# Artemis_Corner_Board_V2_FR.net
KiCad netlist of a schematic drawn in EAGLE
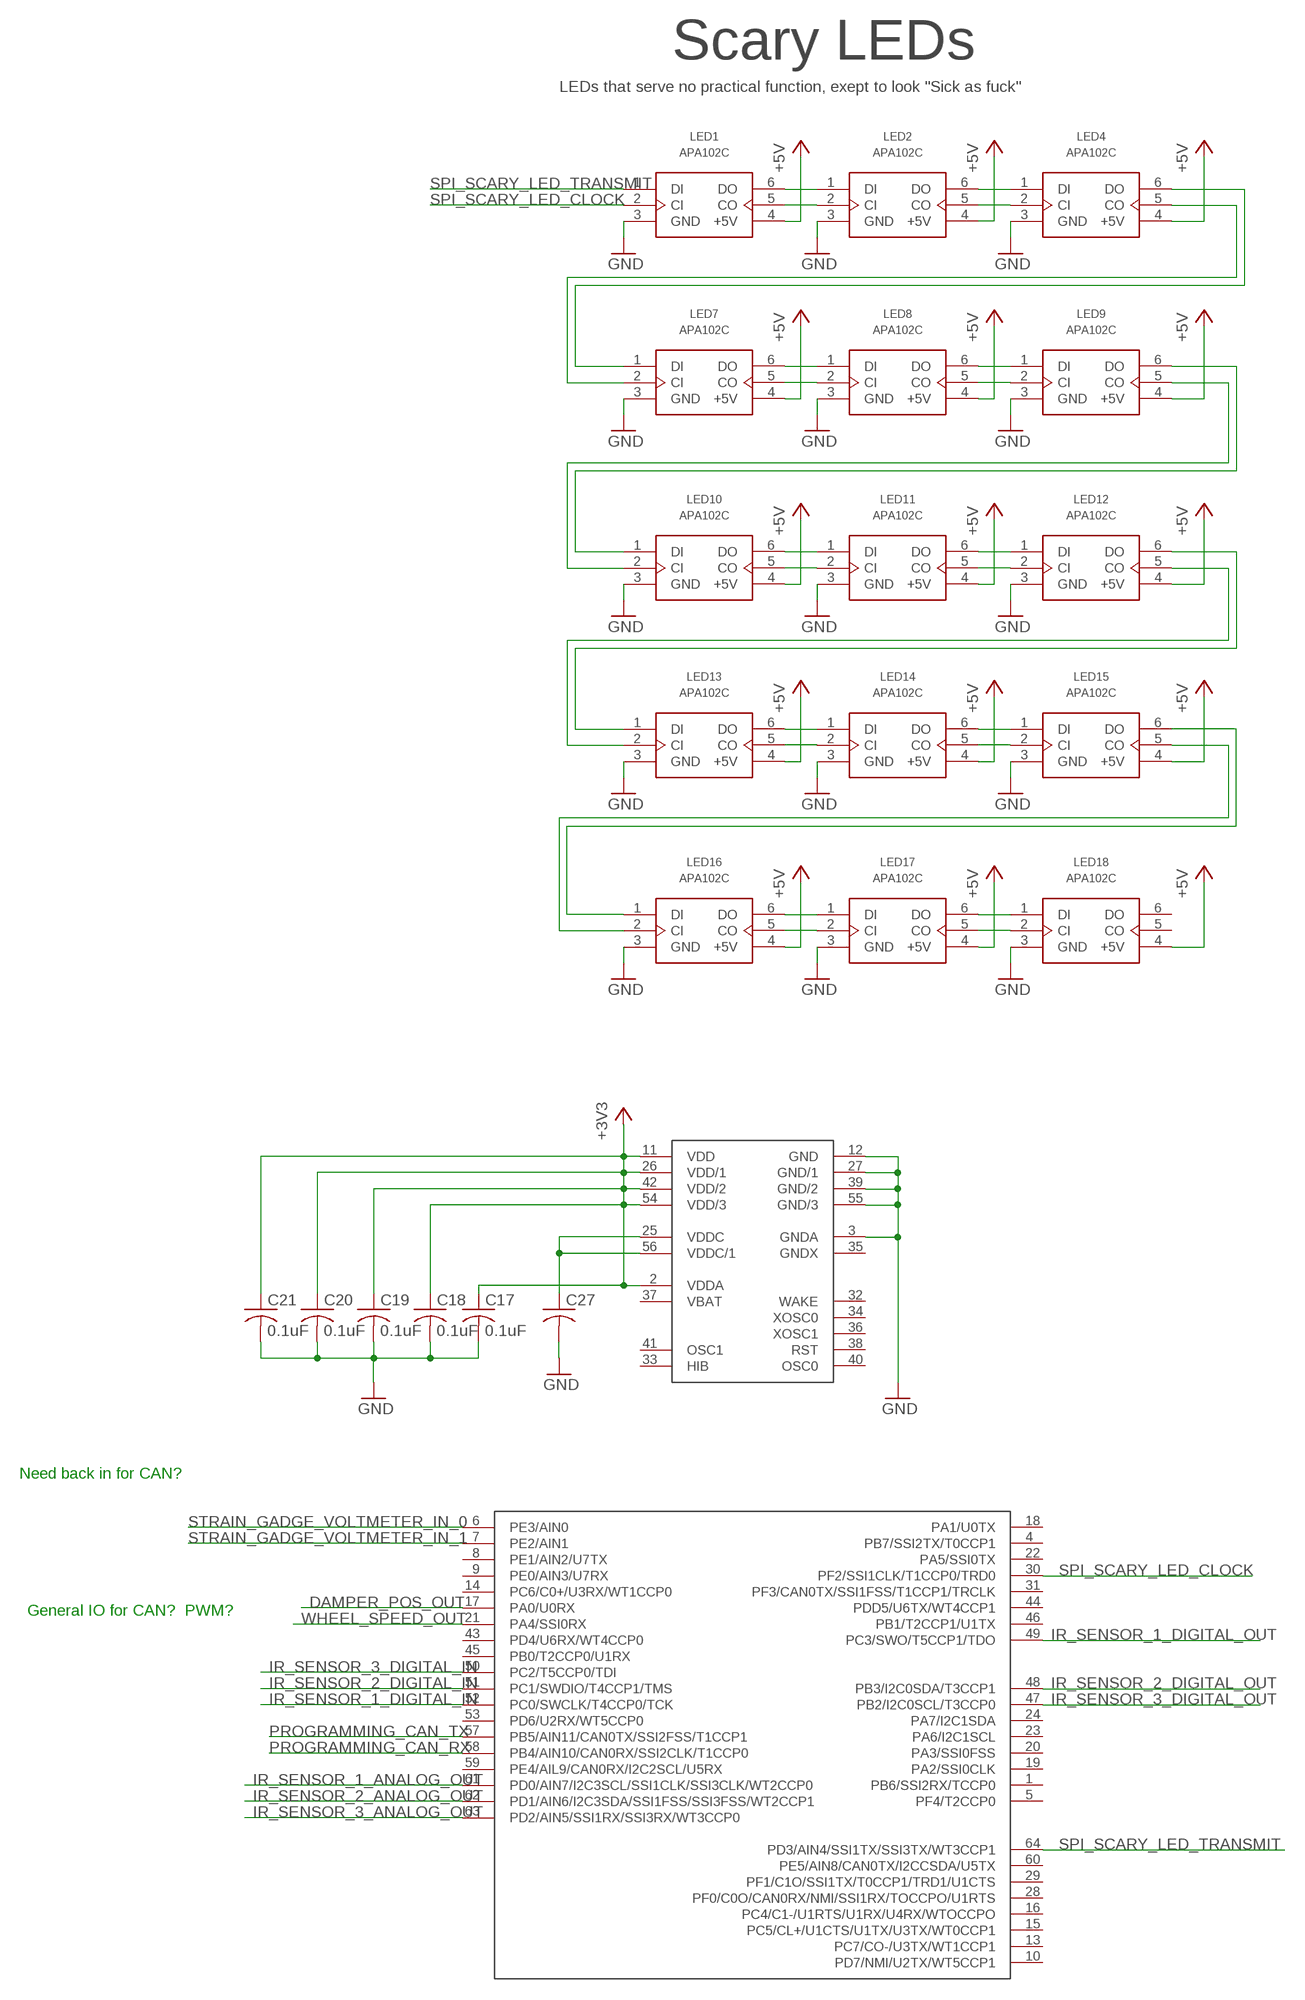
[diagram p0: schematic, sheet 1, part 1 of 2]
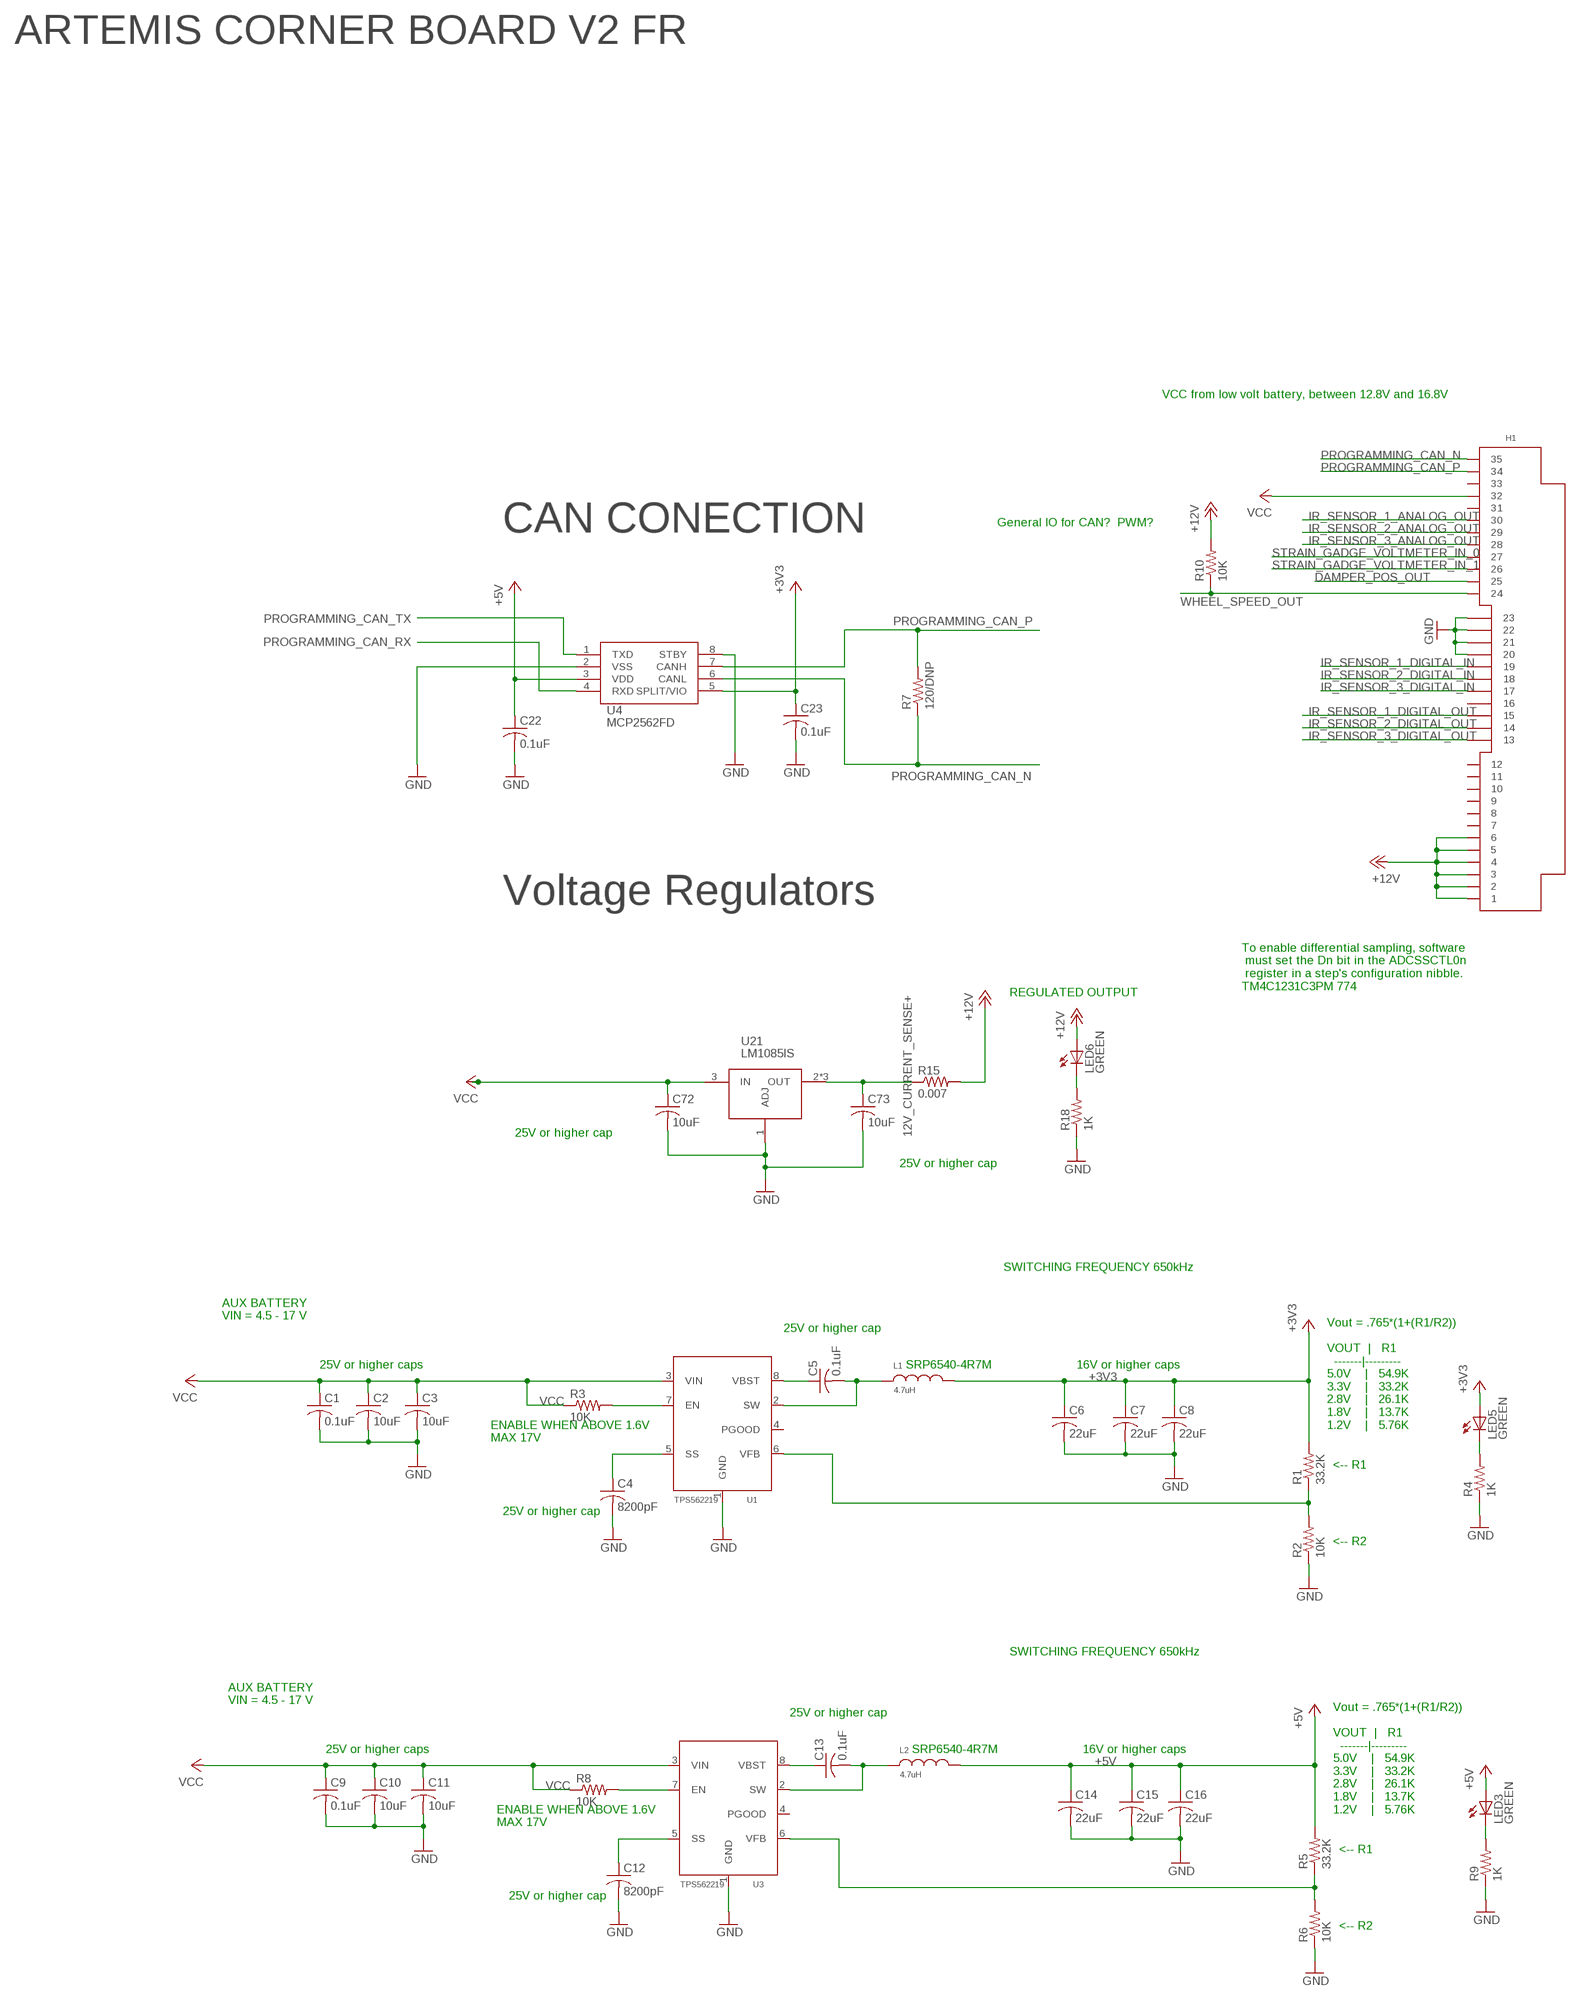
[diagram p1: schematic, sheet 1, part 2 of 2]

(export (version "E")
  (design (tool "Eeschema 10.0.6"))
  (components
    (comp (ref "C1")
      (value "0.1uF")
      (footprint "eagle-import:C0805")
      (fields (field (name "PARTNO") "GRM21BR71E104KA01L"))
      (libsource (lib "eagle-import") (part "C-USC0805"))
    )
    (comp (ref "C2")
      (value "10uF")
      (footprint "eagle-import:C0805")
      (fields (field (name "PARTNO") "GRM21BR61E106KA73L"))
      (libsource (lib "eagle-import") (part "C-USC0805"))
    )
    (comp (ref "C3")
      (value "10uF")
      (footprint "eagle-import:C0805")
      (fields (field (name "PARTNO") "GRM21BR61E106KA73L"))
      (libsource (lib "eagle-import") (part "C-USC0805"))
    )
    (comp (ref "C4")
      (value "8200pF")
      (footprint "eagle-import:C0805")
      (fields (field (name "PARTNO") "C0805C822K5RACTU"))
      (libsource (lib "eagle-import") (part "C-USC0805"))
    )
    (comp (ref "C5")
      (value "0.1uF")
      (footprint "eagle-import:C0805")
      (fields (field (name "PARTNO") "GRM21BR71E104KA01L"))
      (libsource (lib "eagle-import") (part "C-USC0805"))
    )
    (comp (ref "C6")
      (value "22uF")
      (footprint "eagle-import:C0805")
      (fields (field (name "PARTNO") "C2012JB1E226M125AC"))
      (libsource (lib "eagle-import") (part "C-USC0805"))
    )
    (comp (ref "C7")
      (value "22uF")
      (footprint "eagle-import:C0805")
      (fields (field (name "PARTNO") "C2012JB1E226M125AC"))
      (libsource (lib "eagle-import") (part "C-USC0805"))
    )
    (comp (ref "C8")
      (value "22uF")
      (footprint "eagle-import:C0805")
      (fields (field (name "PARTNO") "C2012JB1E226M125AC"))
      (libsource (lib "eagle-import") (part "C-USC0805"))
    )
    (comp (ref "C9")
      (value "0.1uF")
      (footprint "eagle-import:C0805")
      (fields (field (name "PARTNO") "GRM21BR71E104KA01L"))
      (libsource (lib "eagle-import") (part "C-USC0805"))
    )
    (comp (ref "C10")
      (value "10uF")
      (footprint "eagle-import:C0805")
      (fields (field (name "PARTNO") "GRM21BR61E106KA73L"))
      (libsource (lib "eagle-import") (part "C-USC0805"))
    )
    (comp (ref "C11")
      (value "10uF")
      (footprint "eagle-import:C0805")
      (fields (field (name "PARTNO") "GRM21BR61E106KA73L"))
      (libsource (lib "eagle-import") (part "C-USC0805"))
    )
    (comp (ref "C12")
      (value "8200pF")
      (footprint "eagle-import:C0805")
      (fields (field (name "PARTNO") "C0805C822K5RACTU"))
      (libsource (lib "eagle-import") (part "C-USC0805"))
    )
    (comp (ref "C13")
      (value "0.1uF")
      (footprint "eagle-import:C0805")
      (fields (field (name "PARTNO") "GRM21BR71E104KA01L"))
      (libsource (lib "eagle-import") (part "C-USC0805"))
    )
    (comp (ref "C14")
      (value "22uF")
      (footprint "eagle-import:C0805")
      (fields (field (name "PARTNO") "C2012JB1E226M125AC"))
      (libsource (lib "eagle-import") (part "C-USC0805"))
    )
    (comp (ref "C15")
      (value "22uF")
      (footprint "eagle-import:C0805")
      (fields (field (name "PARTNO") "C2012JB1E226M125AC"))
      (libsource (lib "eagle-import") (part "C-USC0805"))
    )
    (comp (ref "C16")
      (value "22uF")
      (footprint "eagle-import:C0805")
      (fields (field (name "PARTNO") "C2012JB1E226M125AC"))
      (libsource (lib "eagle-import") (part "C-USC0805"))
    )
    (comp (ref "C17")
      (value "0.1uF")
      (footprint "eagle-import:C0805")
      (fields (field (name "PARTNO") "GRM21BR71H104KA01L"))
      (libsource (lib "eagle-import") (part "rcl_C-USC0805"))
    )
    (comp (ref "C18")
      (value "0.1uF")
      (footprint "eagle-import:C0805")
      (fields (field (name "PARTNO") "GRM21BR71H104KA01L"))
      (libsource (lib "eagle-import") (part "rcl_C-USC0805"))
    )
    (comp (ref "C19")
      (value "0.1uF")
      (footprint "eagle-import:C0805")
      (fields (field (name "PARTNO") "GRM21BR71H104KA01L"))
      (libsource (lib "eagle-import") (part "rcl_C-USC0805"))
    )
    (comp (ref "C20")
      (value "0.1uF")
      (footprint "eagle-import:C0805")
      (fields (field (name "PARTNO") "GRM21BR71H104KA01L"))
      (libsource (lib "eagle-import") (part "rcl_C-USC0805"))
    )
    (comp (ref "C21")
      (value "0.1uF")
      (footprint "eagle-import:C0805")
      (fields (field (name "PARTNO") "GRM21BR71H104KA01L"))
      (libsource (lib "eagle-import") (part "rcl_C-USC0805"))
    )
    (comp (ref "C22")
      (value "0.1uF")
      (footprint "eagle-import:C0805")
      (fields (field (name "PARTNO") "GRM21BR71H104KA01L"))
      (libsource (lib "eagle-import") (part "rcl_C-USC0805"))
    )
    (comp (ref "C23")
      (value "0.1uF")
      (footprint "eagle-import:C0805")
      (fields (field (name "PARTNO") "GRM21BR71H104KA01L"))
      (libsource (lib "eagle-import") (part "rcl_C-USC0805"))
    )
    (comp (ref "C27")
      (value "3.3uF")
      (footprint "eagle-import:C0805")
      (fields (field (name "MPN") "C1005X7R1E104K050BB") (field (name "PARTNO") "GRM21BR71E104KA01L"))
      (libsource (lib "eagle-import") (part "rcl_C-USC0805"))
    )
    (comp (ref "C72")
      (value "10uF")
      (footprint "eagle-import:C0805")
      (fields (field (name "PARTNO") "GRM21BR61E106KA73L"))
      (libsource (lib "eagle-import") (part "C-USC0805"))
    )
    (comp (ref "C73")
      (value "10uF")
      (footprint "eagle-import:C0805")
      (fields (field (name "PARTNO") "GRM21BR61E106KA73L"))
      (libsource (lib "eagle-import") (part "C-USC0805"))
    )
    (comp (ref "H1")
      (value "1-776231-1")
      (footprint "eagle-import:1-776231-1")
      (libsource (lib "eagle-import") (part "1-776231-1"))
    )
    (comp (ref "L1")
      (value "4.7uH")
      (footprint "eagle-import:SRP6540")
      (fields (field (name "PARTNO") "SRP6540-4R7M"))
      (libsource (lib "eagle-import") (part "SRP6540"))
    )
    (comp (ref "L2")
      (value "4.7uH")
      (footprint "eagle-import:SRP6540")
      (fields (field (name "PARTNO") "SRP6540-4R7M"))
      (libsource (lib "eagle-import") (part "SRP6540"))
    )
    (comp (ref "LED1")
      (value "APA102C")
      (footprint "eagle-import:5050_LED")
      (libsource (lib "eagle-import") (part "APA102C"))
    )
    (comp (ref "LED2")
      (value "APA102C")
      (footprint "eagle-import:5050_LED")
      (libsource (lib "eagle-import") (part "APA102C"))
    )
    (comp (ref "LED3")
      (value "GREEN")
      (footprint "eagle-import:CHIPLED_0805")
      (fields (field (name "PARTNO") "598-8170-107F"))
      (libsource (lib "eagle-import") (part "LEDCHIPLED_0805"))
    )
    (comp (ref "LED4")
      (value "APA102C")
      (footprint "eagle-import:5050_LED")
      (libsource (lib "eagle-import") (part "APA102C"))
    )
    (comp (ref "LED5")
      (value "GREEN")
      (footprint "eagle-import:CHIPLED_0805")
      (fields (field (name "PARTNO") "598-8170-107F"))
      (libsource (lib "eagle-import") (part "LEDCHIPLED_0805"))
    )
    (comp (ref "LED6")
      (value "GREEN")
      (footprint "eagle-import:CHIPLED_0805")
      (fields (field (name "PARTNO") "598-8170-107F"))
      (libsource (lib "eagle-import") (part "LEDCHIPLED_0805"))
    )
    (comp (ref "LED7")
      (value "APA102C")
      (footprint "eagle-import:5050_LED")
      (libsource (lib "eagle-import") (part "APA102C"))
    )
    (comp (ref "LED8")
      (value "APA102C")
      (footprint "eagle-import:5050_LED")
      (libsource (lib "eagle-import") (part "APA102C"))
    )
    (comp (ref "LED9")
      (value "APA102C")
      (footprint "eagle-import:5050_LED")
      (libsource (lib "eagle-import") (part "APA102C"))
    )
    (comp (ref "LED10")
      (value "APA102C")
      (footprint "eagle-import:5050_LED")
      (libsource (lib "eagle-import") (part "APA102C"))
    )
    (comp (ref "LED11")
      (value "APA102C")
      (footprint "eagle-import:5050_LED")
      (libsource (lib "eagle-import") (part "APA102C"))
    )
    (comp (ref "LED12")
      (value "APA102C")
      (footprint "eagle-import:5050_LED")
      (libsource (lib "eagle-import") (part "APA102C"))
    )
    (comp (ref "LED13")
      (value "APA102C")
      (footprint "eagle-import:5050_LED")
      (libsource (lib "eagle-import") (part "APA102C"))
    )
    (comp (ref "LED14")
      (value "APA102C")
      (footprint "eagle-import:5050_LED")
      (libsource (lib "eagle-import") (part "APA102C"))
    )
    (comp (ref "LED15")
      (value "APA102C")
      (footprint "eagle-import:5050_LED")
      (libsource (lib "eagle-import") (part "APA102C"))
    )
    (comp (ref "LED16")
      (value "APA102C")
      (footprint "eagle-import:5050_LED")
      (libsource (lib "eagle-import") (part "APA102C"))
    )
    (comp (ref "LED17")
      (value "APA102C")
      (footprint "eagle-import:5050_LED")
      (libsource (lib "eagle-import") (part "APA102C"))
    )
    (comp (ref "LED18")
      (value "APA102C")
      (footprint "eagle-import:5050_LED")
      (libsource (lib "eagle-import") (part "APA102C"))
    )
    (comp (ref "R1")
      (value "33.2K")
      (footprint "eagle-import:R0805")
      (fields (field (name "PARTNO") "ERA-6AEB5492V"))
      (libsource (lib "eagle-import") (part "R-US_R0805"))
    )
    (comp (ref "R2")
      (value "10K")
      (footprint "eagle-import:R0805")
      (fields (field (name "PARTNO") "ERJ-6ENF1002V"))
      (libsource (lib "eagle-import") (part "R-US_R0805"))
    )
    (comp (ref "R3")
      (value "10K")
      (footprint "eagle-import:R0805")
      (fields (field (name "PARTNO") "ERJ-6ENF1002V"))
      (libsource (lib "eagle-import") (part "R-US_R0805"))
    )
    (comp (ref "R4")
      (value "1K")
      (footprint "eagle-import:R0805")
      (fields (field (name "PARTNO") "ERJ-6ENF1001V"))
      (libsource (lib "eagle-import") (part "R-US_R0805"))
    )
    (comp (ref "R5")
      (value "33.2K")
      (footprint "eagle-import:R0805")
      (fields (field (name "PARTNO") "ERA-6AEB5492V"))
      (libsource (lib "eagle-import") (part "R-US_R0805"))
    )
    (comp (ref "R6")
      (value "10K")
      (footprint "eagle-import:R0805")
      (fields (field (name "PARTNO") "ERJ-6ENF1002V"))
      (libsource (lib "eagle-import") (part "R-US_R0805"))
    )
    (comp (ref "R7")
      (value "120/DNP")
      (footprint "eagle-import:R0805")
      (libsource (lib "eagle-import") (part "rcl_R-US_R0805"))
    )
    (comp (ref "R8")
      (value "10K")
      (footprint "eagle-import:R0805")
      (fields (field (name "PARTNO") "ERJ-6ENF1002V"))
      (libsource (lib "eagle-import") (part "R-US_R0805"))
    )
    (comp (ref "R9")
      (value "1K")
      (footprint "eagle-import:R0805")
      (fields (field (name "PARTNO") "ERJ-6ENF1001V"))
      (libsource (lib "eagle-import") (part "R-US_R0805"))
    )
    (comp (ref "R10")
      (value "10K")
      (footprint "eagle-import:R0805")
      (fields (field (name "PARTNO") "ERJ-6ENF1002V"))
      (libsource (lib "eagle-import") (part "R-US_R0805"))
    )
    (comp (ref "R15")
      (value "0.007")
      (footprint "eagle-import:R0805")
      (fields (field (name "PARTNO") "PMR10EZPFU7L00"))
      (libsource (lib "eagle-import") (part "R-US_R0805"))
    )
    (comp (ref "R18")
      (value "1K")
      (footprint "eagle-import:R0805")
      (fields (field (name "PARTNO") "ERJ-6ENF1001V"))
      (libsource (lib "eagle-import") (part "R-US_R0805"))
    )
    (comp (ref "U1")
      (value "TPS562219")
      (footprint "eagle-import:TPS562219")
      (fields (field (name "PARTNO") "TPS562219DDFT"))
      (libsource (lib "eagle-import") (part "TPS562219"))
    )
    (comp (ref "U2")
      (value "TM4C1231C3PM")
      (footprint "eagle-import:TM4C1231C3PM")
      (libsource (lib "eagle-import") (part "TM4C1231C3PM"))
    )
    (comp (ref "U3")
      (value "TPS562219")
      (footprint "eagle-import:TPS562219")
      (fields (field (name "PARTNO") "TPS562219DDFT"))
      (libsource (lib "eagle-import") (part "TPS562219"))
    )
    (comp (ref "U4")
      (value "MCP2562FD")
      (footprint "eagle-import:SOIC8-N_MC")
      (fields (field (name "PARTNO") "MCP2562FD-E/SN"))
      (libsource (lib "eagle-import") (part "MCP256X-SOIC"))
    )
    (comp (ref "U21")
      (value "LM1085IS")
      (footprint "eagle-import:TO-263")
      (fields (field (name "PARTNO") "LM1085IS-12/NOPB"))
      (libsource (lib "eagle-import") (part "LM1085"))
    )
  )
  (nets
    (net (code "1") (name "+3V3") (class "Default")
      (node (ref "C17") (pin "1") (pinfunction "1_1") (pintype "passive"))
      (node (ref "C18") (pin "1") (pinfunction "1_1") (pintype "passive"))
      (node (ref "C19") (pin "1") (pinfunction "1_1") (pintype "passive"))
      (node (ref "C20") (pin "1") (pinfunction "1_1") (pintype "passive"))
      (node (ref "C21") (pin "1") (pinfunction "1_1") (pintype "passive"))
      (node (ref "C23") (pin "1") (pinfunction "1_1") (pintype "passive"))
      (node (ref "C6") (pin "1") (pinfunction "1_1") (pintype "passive"))
      (node (ref "C7") (pin "1") (pinfunction "1_1") (pintype "passive"))
      (node (ref "C8") (pin "1") (pinfunction "1_1") (pintype "passive"))
      (node (ref "L1") (pin "P$2") (pinfunction "P$2_P$2") (pintype "bidirectional"))
      (node (ref "LED5") (pin "A") (pinfunction "A_A") (pintype "passive"))
      (node (ref "R1") (pin "2") (pinfunction "2_2") (pintype "passive"))
      (node (ref "U2") (pin "11") (pinfunction "VDD_11") (pintype "bidirectional"))
      (node (ref "U2") (pin "2") (pinfunction "VDDA_2") (pintype "bidirectional"))
      (node (ref "U2") (pin "26") (pinfunction "VDD/1_26") (pintype "bidirectional"))
      (node (ref "U2") (pin "42") (pinfunction "VDD/2_42") (pintype "bidirectional"))
      (node (ref "U2") (pin "54") (pinfunction "VDD/3_54") (pintype "bidirectional"))
      (node (ref "U4") (pin "5") (pinfunction "SPLIT/VIO_5") (pintype "bidirectional"))
    )
    (net (code "2") (name "+5V") (class "Default")
      (node (ref "C14") (pin "1") (pinfunction "1_1") (pintype "passive"))
      (node (ref "C15") (pin "1") (pinfunction "1_1") (pintype "passive"))
      (node (ref "C16") (pin "1") (pinfunction "1_1") (pintype "passive"))
      (node (ref "C22") (pin "1") (pinfunction "1_1") (pintype "passive"))
      (node (ref "L2") (pin "P$2") (pinfunction "P$2_P$2") (pintype "bidirectional"))
      (node (ref "LED1") (pin "4") (pinfunction "+5V_4") (pintype "power_in"))
      (node (ref "LED10") (pin "4") (pinfunction "+5V_4") (pintype "power_in"))
      (node (ref "LED11") (pin "4") (pinfunction "+5V_4") (pintype "power_in"))
      (node (ref "LED12") (pin "4") (pinfunction "+5V_4") (pintype "power_in"))
      (node (ref "LED13") (pin "4") (pinfunction "+5V_4") (pintype "power_in"))
      (node (ref "LED14") (pin "4") (pinfunction "+5V_4") (pintype "power_in"))
      (node (ref "LED15") (pin "4") (pinfunction "+5V_4") (pintype "power_in"))
      (node (ref "LED16") (pin "4") (pinfunction "+5V_4") (pintype "power_in"))
      (node (ref "LED17") (pin "4") (pinfunction "+5V_4") (pintype "power_in"))
      (node (ref "LED18") (pin "4") (pinfunction "+5V_4") (pintype "power_in"))
      (node (ref "LED2") (pin "4") (pinfunction "+5V_4") (pintype "power_in"))
      (node (ref "LED3") (pin "A") (pinfunction "A_A") (pintype "passive"))
      (node (ref "LED4") (pin "4") (pinfunction "+5V_4") (pintype "power_in"))
      (node (ref "LED7") (pin "4") (pinfunction "+5V_4") (pintype "power_in"))
      (node (ref "LED8") (pin "4") (pinfunction "+5V_4") (pintype "power_in"))
      (node (ref "LED9") (pin "4") (pinfunction "+5V_4") (pintype "power_in"))
      (node (ref "R5") (pin "2") (pinfunction "2_2") (pintype "passive"))
      (node (ref "U4") (pin "3") (pinfunction "VDD_3") (pintype "power_in"))
    )
    (net (code "3") (name "+12V") (class "Default")
      (node (ref "H1") (pin "1") (pinfunction "1_1") (pintype "bidirectional"))
      (node (ref "H1") (pin "2") (pinfunction "2_2") (pintype "bidirectional"))
      (node (ref "H1") (pin "3") (pinfunction "3_3") (pintype "bidirectional"))
      (node (ref "H1") (pin "4") (pinfunction "4_4") (pintype "bidirectional"))
      (node (ref "H1") (pin "5") (pinfunction "5_5") (pintype "bidirectional"))
      (node (ref "H1") (pin "6") (pinfunction "6_6") (pintype "bidirectional"))
      (node (ref "LED6") (pin "A") (pinfunction "A_A") (pintype "passive"))
      (node (ref "R10") (pin "2") (pinfunction "2_2") (pintype "passive"))
      (node (ref "R15") (pin "2") (pinfunction "2_2") (pintype "passive"))
    )
    (net (code "4") (name "/12V_CURRENT_SENSE+") (class "Default")
      (node (ref "C73") (pin "1") (pinfunction "1_1") (pintype "passive"))
      (node (ref "R15") (pin "1") (pinfunction "1_1") (pintype "passive"))
      (node (ref "U21") (pin "2") (pinfunction "OUT_2") (pintype "bidirectional"))
      (node (ref "U21") (pin "GND") (pinfunction "OUT_GND") (pintype "bidirectional"))
      (node (ref "U21") (pin "GND1") (pinfunction "OUT_GND1") (pintype "bidirectional"))
    )
    (net (code "5") (name "/DAMPER_POS_OUT") (class "Default")
      (node (ref "H1") (pin "25") (pinfunction "25_25") (pintype "bidirectional"))
      (node (ref "U2") (pin "17") (pinfunction "PA0/U0RX_17") (pintype "bidirectional"))
    )
    (net (code "6") (name "/IR_SENSOR_1_ANALOG_OUT") (class "Default")
      (node (ref "H1") (pin "30") (pinfunction "30_30") (pintype "bidirectional"))
      (node (ref "U2") (pin "61") (pinfunction "PD0/AIN7/I2C3SCL/SSI1CLK/SSI3CLK/WT2CCP0_61") (pintype "bidirectional"))
    )
    (net (code "7") (name "/IR_SENSOR_1_DIGITAL_IN") (class "Default")
      (node (ref "H1") (pin "19") (pinfunction "19_19") (pintype "bidirectional"))
      (node (ref "U2") (pin "52") (pinfunction "PC0/SWCLK/T4CCP0/TCK_52") (pintype "bidirectional"))
    )
    (net (code "8") (name "/IR_SENSOR_1_DIGITAL_OUT") (class "Default")
      (node (ref "H1") (pin "15") (pinfunction "15_15") (pintype "bidirectional"))
      (node (ref "U2") (pin "49") (pinfunction "PC3/SWO/T5CCP1/TDO_49") (pintype "bidirectional"))
    )
    (net (code "9") (name "/IR_SENSOR_2_ANALOG_OUT") (class "Default")
      (node (ref "H1") (pin "29") (pinfunction "29_29") (pintype "bidirectional"))
      (node (ref "U2") (pin "62") (pinfunction "PD1/AIN6/I2C3SDA/SSI1FSS/SSI3FSS/WT2CCP1_62") (pintype "bidirectional"))
    )
    (net (code "10") (name "/IR_SENSOR_2_DIGITAL_IN") (class "Default")
      (node (ref "H1") (pin "18") (pinfunction "18_18") (pintype "bidirectional"))
      (node (ref "U2") (pin "51") (pinfunction "PC1/SWDIO/T4CCP1/TMS_51") (pintype "bidirectional"))
    )
    (net (code "11") (name "/IR_SENSOR_2_DIGITAL_OUT") (class "Default")
      (node (ref "H1") (pin "14") (pinfunction "14_14") (pintype "bidirectional"))
      (node (ref "U2") (pin "48") (pinfunction "PB3/I2C0SDA/T3CCP1_48") (pintype "bidirectional"))
    )
    (net (code "12") (name "/IR_SENSOR_3_ANALOG_OUT") (class "Default")
      (node (ref "H1") (pin "28") (pinfunction "28_28") (pintype "bidirectional"))
      (node (ref "U2") (pin "63") (pinfunction "PD2/AIN5/SSI1RX/SSI3RX/WT3CCP0_63") (pintype "bidirectional"))
    )
    (net (code "13") (name "/IR_SENSOR_3_DIGITAL_IN") (class "Default")
      (node (ref "H1") (pin "17") (pinfunction "17_17") (pintype "bidirectional"))
      (node (ref "U2") (pin "50") (pinfunction "PC2/T5CCP0/TDI_50") (pintype "bidirectional"))
    )
    (net (code "14") (name "/IR_SENSOR_3_DIGITAL_OUT") (class "Default")
      (node (ref "H1") (pin "13") (pinfunction "13_13") (pintype "bidirectional"))
      (node (ref "U2") (pin "47") (pinfunction "PB2/I2C0SCL/T3CCP0_47") (pintype "bidirectional"))
    )
    (net (code "15") (name "/PROGRAMMING_CAN_N") (class "Default")
      (node (ref "H1") (pin "35") (pinfunction "35_35") (pintype "bidirectional"))
      (node (ref "R7") (pin "1") (pinfunction "1_1") (pintype "passive"))
      (node (ref "U4") (pin "6") (pinfunction "CANL_6") (pintype "bidirectional"))
    )
    (net (code "16") (name "/PROGRAMMING_CAN_P") (class "Default")
      (node (ref "H1") (pin "34") (pinfunction "34_34") (pintype "bidirectional"))
      (node (ref "R7") (pin "2") (pinfunction "2_2") (pintype "passive"))
      (node (ref "U4") (pin "7") (pinfunction "CANH_7") (pintype "bidirectional"))
    )
    (net (code "17") (name "/PROGRAMMING_CAN_RX") (class "Default")
      (node (ref "U2") (pin "58") (pinfunction "PB4/AIN10/CAN0RX/SSI2CLK/T1CCP0_58") (pintype "bidirectional"))
      (node (ref "U4") (pin "4") (pinfunction "RXD_4") (pintype "bidirectional"))
    )
    (net (code "18") (name "/PROGRAMMING_CAN_TX") (class "Default")
      (node (ref "U2") (pin "57") (pinfunction "PB5/AIN11/CAN0TX/SSI2FSS/T1CCP1_57") (pintype "bidirectional"))
      (node (ref "U4") (pin "1") (pinfunction "TXD_1") (pintype "bidirectional"))
    )
    (net (code "19") (name "/SPI_SCARY_LED_CLOCK") (class "Default")
      (node (ref "LED1") (pin "2") (pinfunction "CI_2") (pintype "input"))
      (node (ref "U2") (pin "30") (pinfunction "PF2/SSI1CLK/T1CCP0/TRD0_30") (pintype "bidirectional"))
    )
    (net (code "20") (name "/SPI_SCARY_LED_TRANSMIT") (class "Default")
      (node (ref "LED1") (pin "1") (pinfunction "DI_1") (pintype "input"))
      (node (ref "U2") (pin "64") (pinfunction "PD3/AIN4/SSI1TX/SSI3TX/WT3CCP1_64") (pintype "bidirectional"))
    )
    (net (code "21") (name "/STRAIN_GADGE_VOLTMETER_IN_0") (class "Default")
      (node (ref "H1") (pin "27") (pinfunction "27_27") (pintype "bidirectional"))
      (node (ref "U2") (pin "6") (pinfunction "PE3/AIN0_6") (pintype "bidirectional"))
    )
    (net (code "22") (name "/STRAIN_GADGE_VOLTMETER_IN_1") (class "Default")
      (node (ref "H1") (pin "26") (pinfunction "26_26") (pintype "bidirectional"))
      (node (ref "U2") (pin "7") (pinfunction "PE2/AIN1_7") (pintype "bidirectional"))
    )
    (net (code "23") (name "/WHEEL_SPEED_OUT") (class "Default")
      (node (ref "H1") (pin "24") (pinfunction "24_24") (pintype "bidirectional"))
      (node (ref "R10") (pin "1") (pinfunction "1_1") (pintype "passive"))
      (node (ref "U2") (pin "21") (pinfunction "PA4/SSI0RX_21") (pintype "bidirectional"))
    )
    (net (code "24") (name "GND") (class "Default")
      (node (ref "C1") (pin "2") (pinfunction "2_2") (pintype "passive"))
      (node (ref "C10") (pin "2") (pinfunction "2_2") (pintype "passive"))
      (node (ref "C11") (pin "2") (pinfunction "2_2") (pintype "passive"))
      (node (ref "C12") (pin "2") (pinfunction "2_2") (pintype "passive"))
      (node (ref "C14") (pin "2") (pinfunction "2_2") (pintype "passive"))
      (node (ref "C15") (pin "2") (pinfunction "2_2") (pintype "passive"))
      (node (ref "C16") (pin "2") (pinfunction "2_2") (pintype "passive"))
      (node (ref "C17") (pin "2") (pinfunction "2_2") (pintype "passive"))
      (node (ref "C18") (pin "2") (pinfunction "2_2") (pintype "passive"))
      (node (ref "C19") (pin "2") (pinfunction "2_2") (pintype "passive"))
      (node (ref "C2") (pin "2") (pinfunction "2_2") (pintype "passive"))
      (node (ref "C20") (pin "2") (pinfunction "2_2") (pintype "passive"))
      (node (ref "C21") (pin "2") (pinfunction "2_2") (pintype "passive"))
      (node (ref "C22") (pin "2") (pinfunction "2_2") (pintype "passive"))
      (node (ref "C23") (pin "2") (pinfunction "2_2") (pintype "passive"))
      (node (ref "C27") (pin "2") (pinfunction "2_2") (pintype "passive"))
      (node (ref "C3") (pin "2") (pinfunction "2_2") (pintype "passive"))
      (node (ref "C4") (pin "2") (pinfunction "2_2") (pintype "passive"))
      (node (ref "C6") (pin "2") (pinfunction "2_2") (pintype "passive"))
      (node (ref "C7") (pin "2") (pinfunction "2_2") (pintype "passive"))
      (node (ref "C72") (pin "2") (pinfunction "2_2") (pintype "passive"))
      (node (ref "C73") (pin "2") (pinfunction "2_2") (pintype "passive"))
      (node (ref "C8") (pin "2") (pinfunction "2_2") (pintype "passive"))
      (node (ref "C9") (pin "2") (pinfunction "2_2") (pintype "passive"))
      (node (ref "H1") (pin "20") (pinfunction "20_20") (pintype "bidirectional"))
      (node (ref "H1") (pin "21") (pinfunction "21_21") (pintype "bidirectional"))
      (node (ref "H1") (pin "22") (pinfunction "22_22") (pintype "bidirectional"))
      (node (ref "H1") (pin "23") (pinfunction "23_23") (pintype "bidirectional"))
      (node (ref "LED1") (pin "3") (pinfunction "GND_3") (pintype "power_in"))
      (node (ref "LED10") (pin "3") (pinfunction "GND_3") (pintype "power_in"))
      (node (ref "LED11") (pin "3") (pinfunction "GND_3") (pintype "power_in"))
      (node (ref "LED12") (pin "3") (pinfunction "GND_3") (pintype "power_in"))
      (node (ref "LED13") (pin "3") (pinfunction "GND_3") (pintype "power_in"))
      (node (ref "LED14") (pin "3") (pinfunction "GND_3") (pintype "power_in"))
      (node (ref "LED15") (pin "3") (pinfunction "GND_3") (pintype "power_in"))
      (node (ref "LED16") (pin "3") (pinfunction "GND_3") (pintype "power_in"))
      (node (ref "LED17") (pin "3") (pinfunction "GND_3") (pintype "power_in"))
      (node (ref "LED18") (pin "3") (pinfunction "GND_3") (pintype "power_in"))
      (node (ref "LED2") (pin "3") (pinfunction "GND_3") (pintype "power_in"))
      (node (ref "LED4") (pin "3") (pinfunction "GND_3") (pintype "power_in"))
      (node (ref "LED7") (pin "3") (pinfunction "GND_3") (pintype "power_in"))
      (node (ref "LED8") (pin "3") (pinfunction "GND_3") (pintype "power_in"))
      (node (ref "LED9") (pin "3") (pinfunction "GND_3") (pintype "power_in"))
      (node (ref "R18") (pin "1") (pinfunction "1_1") (pintype "passive"))
      (node (ref "R2") (pin "1") (pinfunction "1_1") (pintype "passive"))
      (node (ref "R4") (pin "1") (pinfunction "1_1") (pintype "passive"))
      (node (ref "R6") (pin "1") (pinfunction "1_1") (pintype "passive"))
      (node (ref "R9") (pin "1") (pinfunction "1_1") (pintype "passive"))
      (node (ref "U1") (pin "1") (pinfunction "GND_1") (pintype "bidirectional"))
      (node (ref "U2") (pin "12") (pinfunction "GND_12") (pintype "bidirectional"))
      (node (ref "U2") (pin "27") (pinfunction "GND/1_27") (pintype "bidirectional"))
      (node (ref "U2") (pin "3") (pinfunction "GNDA_3") (pintype "bidirectional"))
      (node (ref "U2") (pin "39") (pinfunction "GND/2_39") (pintype "bidirectional"))
      (node (ref "U2") (pin "55") (pinfunction "GND/3_55") (pintype "bidirectional"))
      (node (ref "U21") (pin "1") (pinfunction "ADJ_1") (pintype "bidirectional"))
      (node (ref "U3") (pin "1") (pinfunction "GND_1") (pintype "bidirectional"))
      (node (ref "U4") (pin "2") (pinfunction "VSS_2") (pintype "power_in"))
      (node (ref "U4") (pin "8") (pinfunction "STBY_8") (pintype "input"))
    )
    (net (code "25") (name "Net-(LED1-CO)") (class "Default")
      (node (ref "LED1") (pin "5") (pinfunction "CO_5") (pintype "output"))
      (node (ref "LED2") (pin "2") (pinfunction "CI_2") (pintype "input"))
    )
    (net (code "26") (name "Net-(LED1-DO)") (class "Default")
      (node (ref "LED1") (pin "6") (pinfunction "DO_6") (pintype "output"))
      (node (ref "LED2") (pin "1") (pinfunction "DI_1") (pintype "input"))
    )
    (net (code "27") (name "Net-(LED2-CO)") (class "Default")
      (node (ref "LED2") (pin "5") (pinfunction "CO_5") (pintype "output"))
      (node (ref "LED4") (pin "2") (pinfunction "CI_2") (pintype "input"))
    )
    (net (code "28") (name "Net-(LED2-DO)") (class "Default")
      (node (ref "LED2") (pin "6") (pinfunction "DO_6") (pintype "output"))
      (node (ref "LED4") (pin "1") (pinfunction "DI_1") (pintype "input"))
    )
    (net (code "29") (name "Net-(LED3-PadC)") (class "Default")
      (node (ref "LED3") (pin "C") (pinfunction "C_C") (pintype "passive"))
      (node (ref "R9") (pin "2") (pinfunction "2_2") (pintype "passive"))
    )
    (net (code "30") (name "Net-(LED4-CO)") (class "Default")
      (node (ref "LED4") (pin "5") (pinfunction "CO_5") (pintype "output"))
      (node (ref "LED7") (pin "2") (pinfunction "CI_2") (pintype "input"))
    )
    (net (code "31") (name "Net-(LED4-DO)") (class "Default")
      (node (ref "LED4") (pin "6") (pinfunction "DO_6") (pintype "output"))
      (node (ref "LED7") (pin "1") (pinfunction "DI_1") (pintype "input"))
    )
    (net (code "32") (name "Net-(LED5-PadC)") (class "Default")
      (node (ref "LED5") (pin "C") (pinfunction "C_C") (pintype "passive"))
      (node (ref "R4") (pin "2") (pinfunction "2_2") (pintype "passive"))
    )
    (net (code "33") (name "Net-(LED6-PadC)") (class "Default")
      (node (ref "LED6") (pin "C") (pinfunction "C_C") (pintype "passive"))
      (node (ref "R18") (pin "2") (pinfunction "2_2") (pintype "passive"))
    )
    (net (code "34") (name "Net-(LED7-CO)") (class "Default")
      (node (ref "LED7") (pin "5") (pinfunction "CO_5") (pintype "output"))
      (node (ref "LED8") (pin "2") (pinfunction "CI_2") (pintype "input"))
    )
    (net (code "35") (name "Net-(LED7-DO)") (class "Default")
      (node (ref "LED7") (pin "6") (pinfunction "DO_6") (pintype "output"))
      (node (ref "LED8") (pin "1") (pinfunction "DI_1") (pintype "input"))
    )
    (net (code "36") (name "Net-(LED8-CO)") (class "Default")
      (node (ref "LED8") (pin "5") (pinfunction "CO_5") (pintype "output"))
      (node (ref "LED9") (pin "2") (pinfunction "CI_2") (pintype "input"))
    )
    (net (code "37") (name "Net-(LED8-DO)") (class "Default")
      (node (ref "LED8") (pin "6") (pinfunction "DO_6") (pintype "output"))
      (node (ref "LED9") (pin "1") (pinfunction "DI_1") (pintype "input"))
    )
    (net (code "38") (name "Net-(LED10-CI)") (class "Default")
      (node (ref "LED10") (pin "2") (pinfunction "CI_2") (pintype "input"))
      (node (ref "LED9") (pin "5") (pinfunction "CO_5") (pintype "output"))
    )
    (net (code "39") (name "Net-(LED10-CO)") (class "Default")
      (node (ref "LED10") (pin "5") (pinfunction "CO_5") (pintype "output"))
      (node (ref "LED11") (pin "2") (pinfunction "CI_2") (pintype "input"))
    )
    (net (code "40") (name "Net-(LED10-DI)") (class "Default")
      (node (ref "LED10") (pin "1") (pinfunction "DI_1") (pintype "input"))
      (node (ref "LED9") (pin "6") (pinfunction "DO_6") (pintype "output"))
    )
    (net (code "41") (name "Net-(LED10-DO)") (class "Default")
      (node (ref "LED10") (pin "6") (pinfunction "DO_6") (pintype "output"))
      (node (ref "LED11") (pin "1") (pinfunction "DI_1") (pintype "input"))
    )
    (net (code "42") (name "Net-(LED11-CO)") (class "Default")
      (node (ref "LED11") (pin "5") (pinfunction "CO_5") (pintype "output"))
      (node (ref "LED12") (pin "2") (pinfunction "CI_2") (pintype "input"))
    )
    (net (code "43") (name "Net-(LED11-DO)") (class "Default")
      (node (ref "LED11") (pin "6") (pinfunction "DO_6") (pintype "output"))
      (node (ref "LED12") (pin "1") (pinfunction "DI_1") (pintype "input"))
    )
    (net (code "44") (name "Net-(LED12-CO)") (class "Default")
      (node (ref "LED12") (pin "5") (pinfunction "CO_5") (pintype "output"))
      (node (ref "LED13") (pin "2") (pinfunction "CI_2") (pintype "input"))
    )
    (net (code "45") (name "Net-(LED12-DO)") (class "Default")
      (node (ref "LED12") (pin "6") (pinfunction "DO_6") (pintype "output"))
      (node (ref "LED13") (pin "1") (pinfunction "DI_1") (pintype "input"))
    )
    (net (code "46") (name "Net-(LED13-CO)") (class "Default")
      (node (ref "LED13") (pin "5") (pinfunction "CO_5") (pintype "output"))
      (node (ref "LED14") (pin "2") (pinfunction "CI_2") (pintype "input"))
    )
    (net (code "47") (name "Net-(LED13-DO)") (class "Default")
      (node (ref "LED13") (pin "6") (pinfunction "DO_6") (pintype "output"))
      (node (ref "LED14") (pin "1") (pinfunction "DI_1") (pintype "input"))
    )
    (net (code "48") (name "Net-(LED14-CO)") (class "Default")
      (node (ref "LED14") (pin "5") (pinfunction "CO_5") (pintype "output"))
      (node (ref "LED15") (pin "2") (pinfunction "CI_2") (pintype "input"))
    )
    (net (code "49") (name "Net-(LED14-DO)") (class "Default")
      (node (ref "LED14") (pin "6") (pinfunction "DO_6") (pintype "output"))
      (node (ref "LED15") (pin "1") (pinfunction "DI_1") (pintype "input"))
    )
    (net (code "50") (name "Net-(LED15-CO)") (class "Default")
      (node (ref "LED15") (pin "5") (pinfunction "CO_5") (pintype "output"))
      (node (ref "LED16") (pin "2") (pinfunction "CI_2") (pintype "input"))
    )
    (net (code "51") (name "Net-(LED15-DO)") (class "Default")
      (node (ref "LED15") (pin "6") (pinfunction "DO_6") (pintype "output"))
      (node (ref "LED16") (pin "1") (pinfunction "DI_1") (pintype "input"))
    )
    (net (code "52") (name "Net-(LED16-CO)") (class "Default")
      (node (ref "LED16") (pin "5") (pinfunction "CO_5") (pintype "output"))
      (node (ref "LED17") (pin "2") (pinfunction "CI_2") (pintype "input"))
    )
    (net (code "53") (name "Net-(LED16-DO)") (class "Default")
      (node (ref "LED16") (pin "6") (pinfunction "DO_6") (pintype "output"))
      (node (ref "LED17") (pin "1") (pinfunction "DI_1") (pintype "input"))
    )
    (net (code "54") (name "Net-(LED17-CO)") (class "Default")
      (node (ref "LED17") (pin "5") (pinfunction "CO_5") (pintype "output"))
      (node (ref "LED18") (pin "2") (pinfunction "CI_2") (pintype "input"))
    )
    (net (code "55") (name "Net-(LED17-DO)") (class "Default")
      (node (ref "LED17") (pin "6") (pinfunction "DO_6") (pintype "output"))
      (node (ref "LED18") (pin "1") (pinfunction "DI_1") (pintype "input"))
    )
    (net (code "56") (name "Net-(U1-EN)") (class "Default")
      (node (ref "R3") (pin "2") (pinfunction "2_2") (pintype "passive"))
      (node (ref "U1") (pin "7") (pinfunction "EN_7") (pintype "bidirectional"))
    )
    (net (code "57") (name "Net-(U1-SS)") (class "Default")
      (node (ref "C4") (pin "1") (pinfunction "1_1") (pintype "passive"))
      (node (ref "U1") (pin "5") (pinfunction "SS_5") (pintype "bidirectional"))
    )
    (net (code "58") (name "Net-(U1-SW)") (class "Default")
      (node (ref "C5") (pin "2") (pinfunction "2_2") (pintype "passive"))
      (node (ref "L1") (pin "P$1") (pinfunction "P$1_P$1") (pintype "bidirectional"))
      (node (ref "U1") (pin "2") (pinfunction "SW_2") (pintype "bidirectional"))
    )
    (net (code "59") (name "Net-(U1-VBST)") (class "Default")
      (node (ref "C5") (pin "1") (pinfunction "1_1") (pintype "passive"))
      (node (ref "U1") (pin "8") (pinfunction "VBST_8") (pintype "bidirectional"))
    )
    (net (code "60") (name "Net-(U1-VFB)") (class "Default")
      (node (ref "R1") (pin "1") (pinfunction "1_1") (pintype "passive"))
      (node (ref "R2") (pin "2") (pinfunction "2_2") (pintype "passive"))
      (node (ref "U1") (pin "6") (pinfunction "VFB_6") (pintype "bidirectional"))
    )
    (net (code "61") (name "Net-(U2-VDDC)") (class "Default")
      (node (ref "C27") (pin "1") (pinfunction "1_1") (pintype "passive"))
      (node (ref "U2") (pin "25") (pinfunction "VDDC_25") (pintype "bidirectional"))
      (node (ref "U2") (pin "56") (pinfunction "VDDC/1_56") (pintype "bidirectional"))
    )
    (net (code "62") (name "Net-(U3-EN)") (class "Default")
      (node (ref "R8") (pin "2") (pinfunction "2_2") (pintype "passive"))
      (node (ref "U3") (pin "7") (pinfunction "EN_7") (pintype "bidirectional"))
    )
    (net (code "63") (name "Net-(U3-SS)") (class "Default")
      (node (ref "C12") (pin "1") (pinfunction "1_1") (pintype "passive"))
      (node (ref "U3") (pin "5") (pinfunction "SS_5") (pintype "bidirectional"))
    )
    (net (code "64") (name "Net-(U3-SW)") (class "Default")
      (node (ref "C13") (pin "2") (pinfunction "2_2") (pintype "passive"))
      (node (ref "L2") (pin "P$1") (pinfunction "P$1_P$1") (pintype "bidirectional"))
      (node (ref "U3") (pin "2") (pinfunction "SW_2") (pintype "bidirectional"))
    )
    (net (code "65") (name "Net-(U3-VBST)") (class "Default")
      (node (ref "C13") (pin "1") (pinfunction "1_1") (pintype "passive"))
      (node (ref "U3") (pin "8") (pinfunction "VBST_8") (pintype "bidirectional"))
    )
    (net (code "66") (name "Net-(U3-VFB)") (class "Default")
      (node (ref "R5") (pin "1") (pinfunction "1_1") (pintype "passive"))
      (node (ref "R6") (pin "2") (pinfunction "2_2") (pintype "passive"))
      (node (ref "U3") (pin "6") (pinfunction "VFB_6") (pintype "bidirectional"))
    )
    (net (code "67") (name "VCC") (class "Default")
      (node (ref "C1") (pin "1") (pinfunction "1_1") (pintype "passive"))
      (node (ref "C10") (pin "1") (pinfunction "1_1") (pintype "passive"))
      (node (ref "C11") (pin "1") (pinfunction "1_1") (pintype "passive"))
      (node (ref "C2") (pin "1") (pinfunction "1_1") (pintype "passive"))
      (node (ref "C3") (pin "1") (pinfunction "1_1") (pintype "passive"))
      (node (ref "C72") (pin "1") (pinfunction "1_1") (pintype "passive"))
      (node (ref "C9") (pin "1") (pinfunction "1_1") (pintype "passive"))
      (node (ref "H1") (pin "32") (pinfunction "32_32") (pintype "bidirectional"))
      (node (ref "R3") (pin "1") (pinfunction "1_1") (pintype "passive"))
      (node (ref "R8") (pin "1") (pinfunction "1_1") (pintype "passive"))
      (node (ref "U1") (pin "3") (pinfunction "VIN_3") (pintype "bidirectional"))
      (node (ref "U21") (pin "3") (pinfunction "IN_3") (pintype "bidirectional"))
      (node (ref "U3") (pin "3") (pinfunction "VIN_3") (pintype "bidirectional"))
    )
    (net (code "68") (name "unconnected-(H1-Pad7)") (class "Default")
      (node (ref "H1") (pin "7") (pinfunction "7_7") (pintype "bidirectional"))
    )
    (net (code "69") (name "unconnected-(H1-Pad8)") (class "Default")
      (node (ref "H1") (pin "8") (pinfunction "8_8") (pintype "bidirectional"))
    )
    (net (code "70") (name "unconnected-(H1-Pad9)") (class "Default")
      (node (ref "H1") (pin "9") (pinfunction "9_9") (pintype "bidirectional"))
    )
    (net (code "71") (name "unconnected-(H1-Pad10)") (class "Default")
      (node (ref "H1") (pin "10") (pinfunction "10_10") (pintype "bidirectional"))
    )
    (net (code "72") (name "unconnected-(H1-Pad11)") (class "Default")
      (node (ref "H1") (pin "11") (pinfunction "11_11") (pintype "bidirectional"))
    )
    (net (code "73") (name "unconnected-(H1-Pad12)") (class "Default")
      (node (ref "H1") (pin "12") (pinfunction "12_12") (pintype "bidirectional"))
    )
    (net (code "74") (name "unconnected-(H1-Pad16)") (class "Default")
      (node (ref "H1") (pin "16") (pinfunction "16_16") (pintype "bidirectional"))
    )
    (net (code "75") (name "unconnected-(H1-Pad31)") (class "Default")
      (node (ref "H1") (pin "31") (pinfunction "31_31") (pintype "bidirectional"))
    )
    (net (code "76") (name "unconnected-(H1-Pad33)") (class "Default")
      (node (ref "H1") (pin "33") (pinfunction "33_33") (pintype "bidirectional"))
    )
    (net (code "77") (name "unconnected-(LED18-CO-Pad5)") (class "Default")
      (node (ref "LED18") (pin "5") (pinfunction "CO_5") (pintype "output"))
    )
    (net (code "78") (name "unconnected-(LED18-DO-Pad6)") (class "Default")
      (node (ref "LED18") (pin "6") (pinfunction "DO_6") (pintype "output"))
    )
    (net (code "79") (name "unconnected-(U1-PGOOD-Pad4)") (class "Default")
      (node (ref "U1") (pin "4") (pinfunction "PGOOD_4") (pintype "bidirectional"))
    )
    (net (code "80") (name "unconnected-(U2-GNDX-Pad35)") (class "Default")
      (node (ref "U2") (pin "35") (pinfunction "GNDX_35") (pintype "bidirectional"))
    )
    (net (code "81") (name "unconnected-(U2-HIB-Pad33)") (class "Default")
      (node (ref "U2") (pin "33") (pinfunction "HIB_33") (pintype "bidirectional"))
    )
    (net (code "82") (name "unconnected-(U2-OSC0-Pad40)") (class "Default")
      (node (ref "U2") (pin "40") (pinfunction "OSC0_40") (pintype "bidirectional"))
    )
    (net (code "83") (name "unconnected-(U2-OSC1-Pad41)") (class "Default")
      (node (ref "U2") (pin "41") (pinfunction "OSC1_41") (pintype "bidirectional"))
    )
    (net (code "84") (name "unconnected-(U2-PA1{slash}U0TX-Pad18)") (class "Default")
      (node (ref "U2") (pin "18") (pinfunction "PA1/U0TX_18") (pintype "bidirectional"))
    )
    (net (code "85") (name "unconnected-(U2-PA2{slash}SSI0CLK-Pad19)") (class "Default")
      (node (ref "U2") (pin "19") (pinfunction "PA2/SSI0CLK_19") (pintype "bidirectional"))
    )
    (net (code "86") (name "unconnected-(U2-PA3{slash}SSI0FSS-Pad20)") (class "Default")
      (node (ref "U2") (pin "20") (pinfunction "PA3/SSI0FSS_20") (pintype "bidirectional"))
    )
    (net (code "87") (name "unconnected-(U2-PA5{slash}SSI0TX-Pad22)") (class "Default")
      (node (ref "U2") (pin "22") (pinfunction "PA5/SSI0TX_22") (pintype "bidirectional"))
    )
    (net (code "88") (name "unconnected-(U2-PA6{slash}I2C1SCL-Pad23)") (class "Default")
      (node (ref "U2") (pin "23") (pinfunction "PA6/I2C1SCL_23") (pintype "bidirectional"))
    )
    (net (code "89") (name "unconnected-(U2-PA7{slash}I2C1SDA-Pad24)") (class "Default")
      (node (ref "U2") (pin "24") (pinfunction "PA7/I2C1SDA_24") (pintype "bidirectional"))
    )
    (net (code "90") (name "unconnected-(U2-PB0{slash}T2CCP0{slash}U1RX-Pad45)") (class "Default")
      (node (ref "U2") (pin "45") (pinfunction "PB0/T2CCP0/U1RX_45") (pintype "bidirectional"))
    )
    (net (code "91") (name "unconnected-(U2-PB1{slash}T2CCP1{slash}U1TX-Pad46)") (class "Default")
      (node (ref "U2") (pin "46") (pinfunction "PB1/T2CCP1/U1TX_46") (pintype "bidirectional"))
    )
    (net (code "92") (name "unconnected-(U2-PB6{slash}SSI2RX{slash}TCCP0-Pad1)") (class "Default")
      (node (ref "U2") (pin "1") (pinfunction "PB6/SSI2RX/TCCP0_1") (pintype "bidirectional"))
    )
    (net (code "93") (name "unconnected-(U2-PB7{slash}SSI2TX{slash}T0CCP1-Pad4)") (class "Default")
      (node (ref "U2") (pin "4") (pinfunction "PB7/SSI2TX/T0CCP1_4") (pintype "bidirectional"))
    )
    (net (code "94") (name "unconnected-(U2-PC4{slash}C1-{slash}U1RTS{slash}U1RX{slash}U4RX{slash}WTOCCPO-Pad16)") (class "Default")
      (node (ref "U2") (pin "16") (pinfunction "PC4/C1-/U1RTS/U1RX/U4RX/WTOCCPO_16") (pintype "bidirectional"))
    )
    (net (code "95") (name "unconnected-(U2-PC5{slash}CL+{slash}U1CTS{slash}U1TX{slash}U3TX{slash}WT0CCP1-Pad15)") (class "Default")
      (node (ref "U2") (pin "15") (pinfunction "PC5/CL+/U1CTS/U1TX/U3TX/WT0CCP1_15") (pintype "bidirectional"))
    )
    (net (code "96") (name "unconnected-(U2-PC6{slash}C0+{slash}U3RX{slash}WT1CCP0-Pad14)") (class "Default")
      (node (ref "U2") (pin "14") (pinfunction "PC6/C0+/U3RX/WT1CCP0_14") (pintype "bidirectional"))
    )
    (net (code "97") (name "unconnected-(U2-PC7{slash}CO-{slash}U3TX{slash}WT1CCP1-Pad13)") (class "Default")
      (node (ref "U2") (pin "13") (pinfunction "PC7/CO-/U3TX/WT1CCP1_13") (pintype "bidirectional"))
    )
    (net (code "98") (name "unconnected-(U2-PD4{slash}U6RX{slash}WT4CCP0-Pad43)") (class "Default")
      (node (ref "U2") (pin "43") (pinfunction "PD4/U6RX/WT4CCP0_43") (pintype "bidirectional"))
    )
    (net (code "99") (name "unconnected-(U2-PD6{slash}U2RX{slash}WT5CCP0-Pad53)") (class "Default")
      (node (ref "U2") (pin "53") (pinfunction "PD6/U2RX/WT5CCP0_53") (pintype "bidirectional"))
    )
    (net (code "100") (name "unconnected-(U2-PD7{slash}NMI{slash}U2TX{slash}WT5CCP1-Pad10)") (class "Default")
      (node (ref "U2") (pin "10") (pinfunction "PD7/NMI/U2TX/WT5CCP1_10") (pintype "bidirectional"))
    )
    (net (code "101") (name "unconnected-(U2-PDD5{slash}U6TX{slash}WT4CCP1-Pad44)") (class "Default")
      (node (ref "U2") (pin "44") (pinfunction "PDD5/U6TX/WT4CCP1_44") (pintype "bidirectional"))
    )
    (net (code "102") (name "unconnected-(U2-PE0{slash}AIN3{slash}U7RX-Pad9)") (class "Default")
      (node (ref "U2") (pin "9") (pinfunction "PE0/AIN3/U7RX_9") (pintype "bidirectional"))
    )
    (net (code "103") (name "unconnected-(U2-PE1{slash}AIN2{slash}U7TX-Pad8)") (class "Default")
      (node (ref "U2") (pin "8") (pinfunction "PE1/AIN2/U7TX_8") (pintype "bidirectional"))
    )
    (net (code "104") (name "unconnected-(U2-PE4{slash}AIL9{slash}CAN0RX{slash}I2C2SCL{slash}U5RX-Pad59)") (class "Default")
      (node (ref "U2") (pin "59") (pinfunction "PE4/AIL9/CAN0RX/I2C2SCL/U5RX_59") (pintype "bidirectional"))
    )
    (net (code "105") (name "unconnected-(U2-PE5{slash}AIN8{slash}CAN0TX{slash}I2CCSDA{slash}U5TX-Pad60)") (class "Default")
      (node (ref "U2") (pin "60") (pinfunction "PE5/AIN8/CAN0TX/I2CCSDA/U5TX_60") (pintype "bidirectional"))
    )
    (net (code "106") (name "unconnected-(U2-PF0{slash}C0O{slash}CAN0RX{slash}NMI{slash}SSI1RX{slash}TOCCPO{slash}U1RTS-Pad28)") (class "Default")
      (node (ref "U2") (pin "28") (pinfunction "PF0/C0O/CAN0RX/NMI/SSI1RX/TOCCPO/U1RTS_28") (pintype "bidirectional"))
    )
    (net (code "107") (name "unconnected-(U2-PF1{slash}C1O{slash}SSI1TX{slash}T0CCP1{slash}TRD1{slash}U1CTS-Pad29)") (class "Default")
      (node (ref "U2") (pin "29") (pinfunction "PF1/C1O/SSI1TX/T0CCP1/TRD1/U1CTS_29") (pintype "bidirectional"))
    )
    (net (code "108") (name "unconnected-(U2-PF3{slash}CAN0TX{slash}SSI1FSS{slash}T1CCP1{slash}TRCLK-Pad31)") (class "Default")
      (node (ref "U2") (pin "31") (pinfunction "PF3/CAN0TX/SSI1FSS/T1CCP1/TRCLK_31") (pintype "bidirectional"))
    )
    (net (code "109") (name "unconnected-(U2-PF4{slash}T2CCP0-Pad5)") (class "Default")
      (node (ref "U2") (pin "5") (pinfunction "PF4/T2CCP0_5") (pintype "bidirectional"))
    )
    (net (code "110") (name "unconnected-(U2-RST-Pad38)") (class "Default")
      (node (ref "U2") (pin "38") (pinfunction "RST_38") (pintype "bidirectional"))
    )
    (net (code "111") (name "unconnected-(U2-VBAT-Pad37)") (class "Default")
      (node (ref "U2") (pin "37") (pinfunction "VBAT_37") (pintype "bidirectional"))
    )
    (net (code "112") (name "unconnected-(U2-WAKE-Pad32)") (class "Default")
      (node (ref "U2") (pin "32") (pinfunction "WAKE_32") (pintype "bidirectional"))
    )
    (net (code "113") (name "unconnected-(U2-XOSC0-Pad34)") (class "Default")
      (node (ref "U2") (pin "34") (pinfunction "XOSC0_34") (pintype "bidirectional"))
    )
    (net (code "114") (name "unconnected-(U2-XOSC1-Pad36)") (class "Default")
      (node (ref "U2") (pin "36") (pinfunction "XOSC1_36") (pintype "bidirectional"))
    )
    (net (code "115") (name "unconnected-(U3-PGOOD-Pad4)") (class "Default")
      (node (ref "U3") (pin "4") (pinfunction "PGOOD_4") (pintype "bidirectional"))
    )
  )
)
